# SparkFun_LilyPad-Button.net
KiCad netlist of a schematic drawn in EAGLE
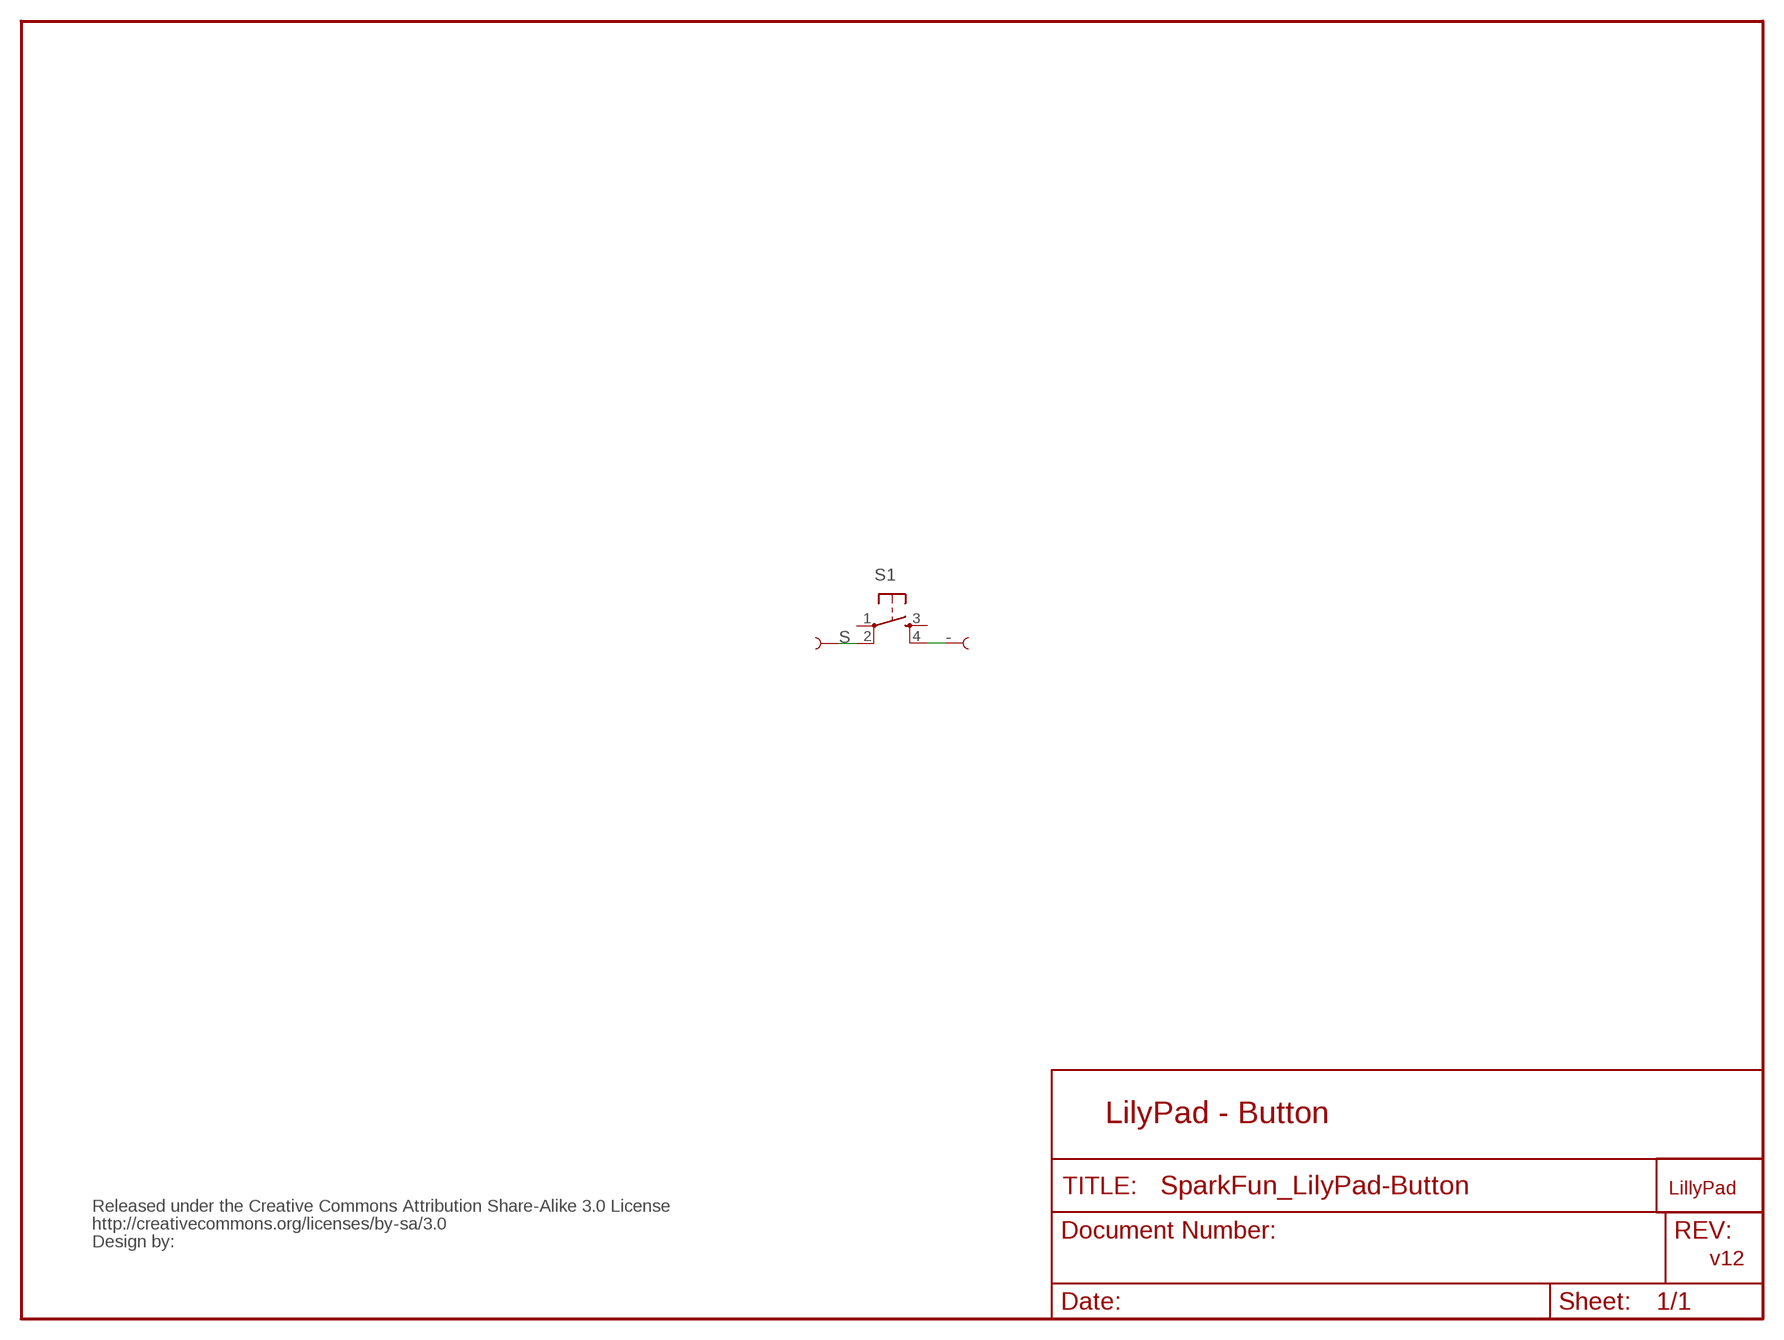
[diagram p0: schematic, sheet 1]

(export (version "E")
  (design (tool "Eeschema 10.0.6"))
  (components
    (comp (ref "BUTTON-")
      (value "SEWTAP8")
      (footprint "eagle-import:PETAL-MEDIUM-2SIDE")
      (libsource (lib "eagle-import") (part "SEWTAP8"))
    )
    (comp (ref "BUTTONS")
      (value "SEWTAP8")
      (footprint "eagle-import:PETAL-MEDIUM-2SIDE")
      (libsource (lib "eagle-import") (part "SEWTAP8"))
    )
    (comp (ref "LOGO1")
      (value "LOGO-LPL")
      (footprint "eagle-import:LOGO-L")
      (libsource (lib "eagle-import") (part "LOGO-LPL"))
    )
    (comp (ref "S1")
      (value "TAC_SWITCHSMD")
      (footprint "eagle-import:TACTILE_SWITCH_SMD")
      (libsource (lib "eagle-import") (part "TAC_SWITCHSMD"))
    )
    (comp (ref "U$1")
      (value "CREATIVE_COMMONS")
      (footprint "eagle-import:CREATIVE_COMMONS")
      (libsource (lib "eagle-import") (part "CREATIVE_COMMONS"))
    )
  )
  (nets
    (net (code "1") (name "/-") (class "Default")
      (node (ref "BUTTON-") (pin "1") (pinfunction "1_1") (pintype "bidirectional"))
      (node (ref "S1") (pin "4") (pinfunction "4_4") (pintype "passive"))
    )
    (net (code "2") (name "/S") (class "Default")
      (node (ref "BUTTONS") (pin "1") (pinfunction "1_1") (pintype "bidirectional"))
      (node (ref "S1") (pin "2") (pinfunction "2_2") (pintype "passive"))
    )
    (net (code "3") (name "unconnected-(S1-Pad1)") (class "Default")
      (node (ref "S1") (pin "1") (pinfunction "1_1") (pintype "passive"))
    )
    (net (code "4") (name "unconnected-(S1-Pad3)") (class "Default")
      (node (ref "S1") (pin "3") (pinfunction "3_3") (pintype "passive"))
    )
  )
)
